# V-00797-00.net
KiCad netlist of a schematic drawn in EAGLE
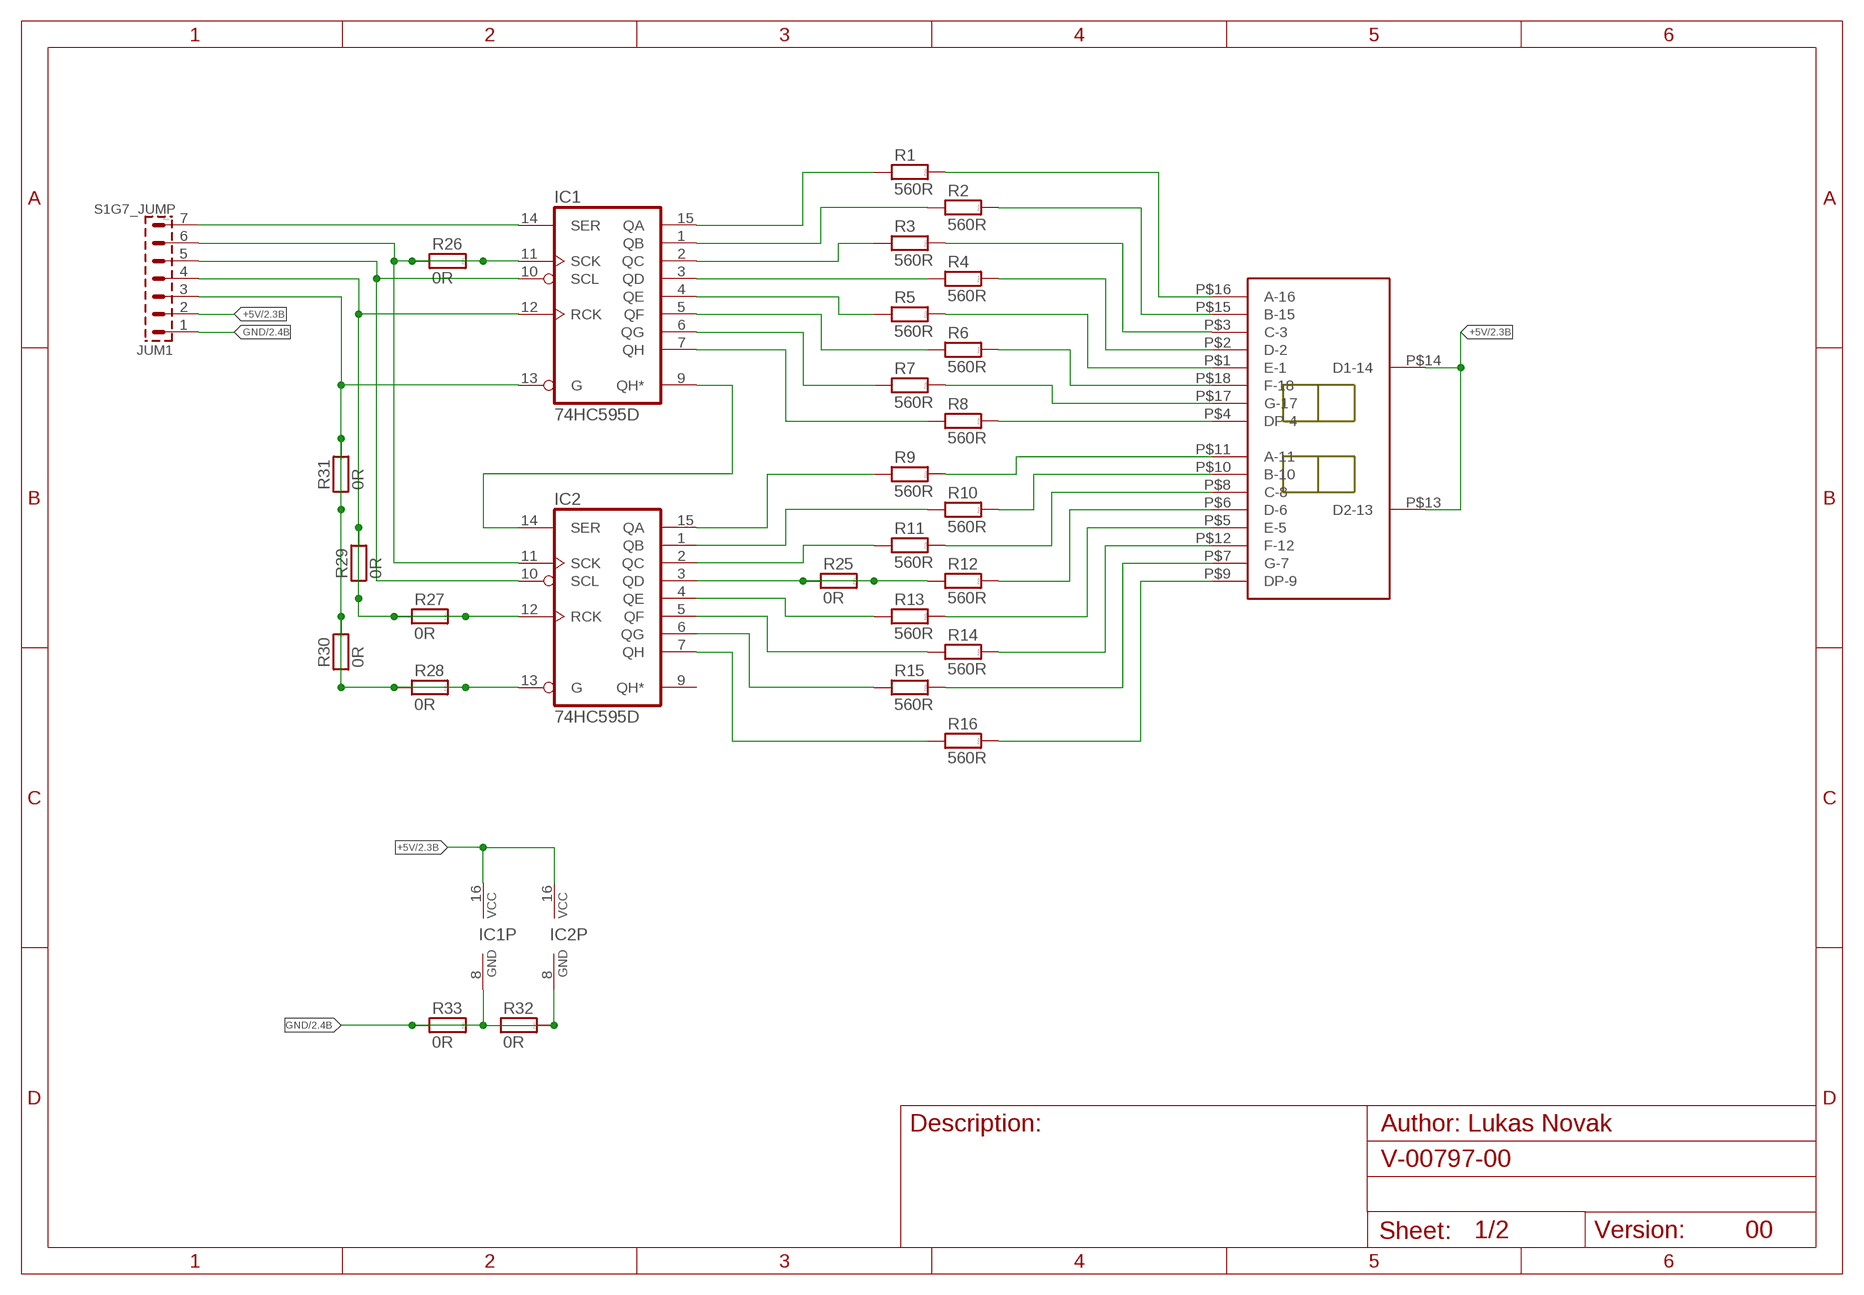
[diagram p0: schematic, sheet 1]
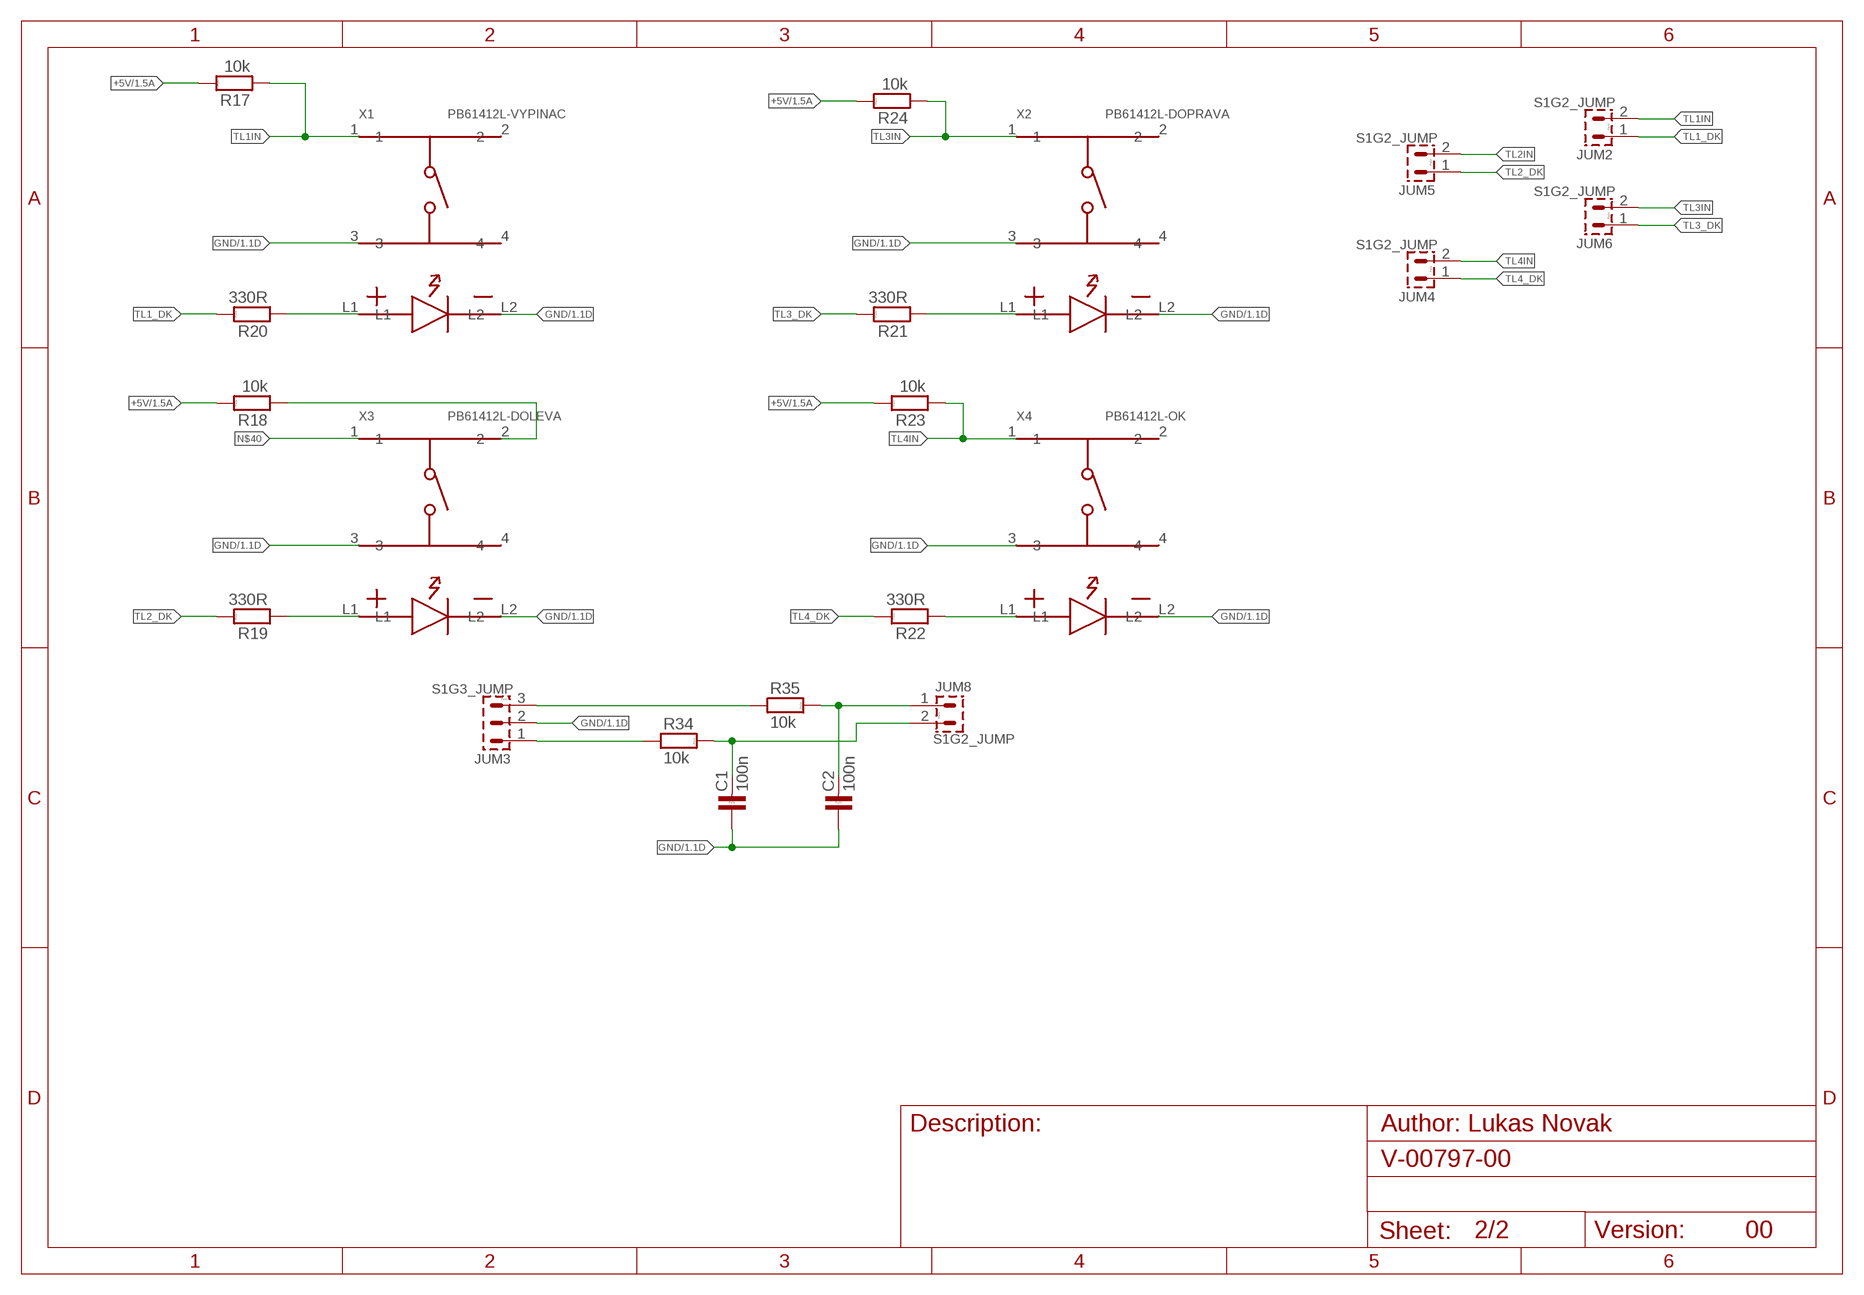
[diagram p1: schematic, sheet 2]

(export (version "E")
  (design (tool "Eeschema 10.0.6"))
  (components
    (comp (ref "IC1")
      (value "74HC595D")
      (footprint "eagle-import:SO16")
      (libsource (lib "eagle-import") (part "74595DHC"))
    )
    (comp (ref "IC2")
      (value "74HC595D")
      (footprint "eagle-import:SO16")
      (libsource (lib "eagle-import") (part "74595DHC"))
    )
    (comp (ref "JUM1")
      (value "S1G7_JUMP")
      (footprint "eagle-import:S1G7_JUM")
      (libsource (lib "eagle-import") (part "S1G7_JUMP"))
    )
    (comp (ref "R1")
      (value "560R")
      (footprint "eagle-import:1206")
      (libsource (lib "eagle-import") (part "R_1206"))
    )
    (comp (ref "R2")
      (value "560R")
      (footprint "eagle-import:1206")
      (libsource (lib "eagle-import") (part "R_1206"))
    )
    (comp (ref "R3")
      (value "560R")
      (footprint "eagle-import:1206")
      (libsource (lib "eagle-import") (part "R_1206"))
    )
    (comp (ref "R4")
      (value "560R")
      (footprint "eagle-import:1206")
      (libsource (lib "eagle-import") (part "R_1206"))
    )
    (comp (ref "R5")
      (value "560R")
      (footprint "eagle-import:1206")
      (libsource (lib "eagle-import") (part "R_1206"))
    )
    (comp (ref "R6")
      (value "560R")
      (footprint "eagle-import:1206")
      (libsource (lib "eagle-import") (part "R_1206"))
    )
    (comp (ref "R7")
      (value "560R")
      (footprint "eagle-import:1206")
      (libsource (lib "eagle-import") (part "R_1206"))
    )
    (comp (ref "R8")
      (value "560R")
      (footprint "eagle-import:1206")
      (libsource (lib "eagle-import") (part "R_1206"))
    )
    (comp (ref "R9")
      (value "560R")
      (footprint "eagle-import:1206")
      (libsource (lib "eagle-import") (part "R_1206"))
    )
    (comp (ref "R10")
      (value "560R")
      (footprint "eagle-import:1206")
      (libsource (lib "eagle-import") (part "R_1206"))
    )
    (comp (ref "R11")
      (value "560R")
      (footprint "eagle-import:1206")
      (libsource (lib "eagle-import") (part "R_1206"))
    )
    (comp (ref "R12")
      (value "560R")
      (footprint "eagle-import:1206")
      (libsource (lib "eagle-import") (part "R_1206"))
    )
    (comp (ref "R13")
      (value "560R")
      (footprint "eagle-import:1206")
      (libsource (lib "eagle-import") (part "R_1206"))
    )
    (comp (ref "R14")
      (value "560R")
      (footprint "eagle-import:1206")
      (libsource (lib "eagle-import") (part "R_1206"))
    )
    (comp (ref "R15")
      (value "560R")
      (footprint "eagle-import:1206")
      (libsource (lib "eagle-import") (part "R_1206"))
    )
    (comp (ref "R16")
      (value "560R")
      (footprint "eagle-import:1206")
      (libsource (lib "eagle-import") (part "R_1206"))
    )
    (comp (ref "R25")
      (value "0R")
      (footprint "eagle-import:1206")
      (libsource (lib "eagle-import") (part "R_1206"))
    )
    (comp (ref "R26")
      (value "0R")
      (footprint "eagle-import:1206")
      (libsource (lib "eagle-import") (part "R_1206"))
    )
    (comp (ref "R27")
      (value "0R")
      (footprint "eagle-import:1206")
      (libsource (lib "eagle-import") (part "R_1206"))
    )
    (comp (ref "R28")
      (value "0R")
      (footprint "eagle-import:1206")
      (libsource (lib "eagle-import") (part "R_1206"))
    )
    (comp (ref "R29")
      (value "0R")
      (footprint "eagle-import:1206")
      (libsource (lib "eagle-import") (part "R_1206"))
    )
    (comp (ref "R30")
      (value "0R")
      (footprint "eagle-import:1206")
      (libsource (lib "eagle-import") (part "R_1206"))
    )
    (comp (ref "R31")
      (value "0R")
      (footprint "eagle-import:1206")
      (libsource (lib "eagle-import") (part "R_1206"))
    )
    (comp (ref "R32")
      (value "0R")
      (footprint "eagle-import:1206")
      (libsource (lib "eagle-import") (part "R_1206"))
    )
    (comp (ref "R33")
      (value "0R")
      (footprint "eagle-import:1206")
      (libsource (lib "eagle-import") (part "R_1206"))
    )
    (comp (ref "U$1")
      (value "BD-A544RD")
      (footprint "eagle-import:BD-A544RD")
      (libsource (lib "eagle-import") (part "BD-A544RD"))
    )
    (comp (ref "C1")
      (value "100n")
      (footprint "eagle-import:1206")
      (libsource (lib "eagle-import") (part "C-KER_1206"))
    )
    (comp (ref "C2")
      (value "100n")
      (footprint "eagle-import:1206")
      (libsource (lib "eagle-import") (part "C-KER_1206"))
    )
    (comp (ref "JUM2")
      (value "S1G2_JUMP")
      (footprint "eagle-import:S1G2_JUM")
      (libsource (lib "eagle-import") (part "S1G2_JUMP"))
    )
    (comp (ref "JUM3")
      (value "S1G3_JUMP")
      (footprint "eagle-import:S1G3_JUM")
      (libsource (lib "eagle-import") (part "S1G3_JUMP"))
    )
    (comp (ref "JUM4")
      (value "S1G2_JUMP")
      (footprint "eagle-import:S1G2_JUM")
      (libsource (lib "eagle-import") (part "S1G2_JUMP"))
    )
    (comp (ref "JUM5")
      (value "S1G2_JUMP")
      (footprint "eagle-import:S1G2_JUM")
      (libsource (lib "eagle-import") (part "S1G2_JUMP"))
    )
    (comp (ref "JUM6")
      (value "S1G2_JUMP")
      (footprint "eagle-import:S1G2_JUM")
      (libsource (lib "eagle-import") (part "S1G2_JUMP"))
    )
    (comp (ref "JUM8")
      (value "S1G2_JUMP")
      (footprint "eagle-import:S1G2_JUM")
      (libsource (lib "eagle-import") (part "S1G2_JUMP"))
    )
    (comp (ref "R17")
      (value "10k")
      (footprint "eagle-import:1206")
      (libsource (lib "eagle-import") (part "R_1206"))
    )
    (comp (ref "R18")
      (value "10k")
      (footprint "eagle-import:1206")
      (libsource (lib "eagle-import") (part "R_1206"))
    )
    (comp (ref "R19")
      (value "330R")
      (footprint "eagle-import:1206")
      (libsource (lib "eagle-import") (part "R_1206"))
    )
    (comp (ref "R20")
      (value "330R")
      (footprint "eagle-import:1206")
      (libsource (lib "eagle-import") (part "R_1206"))
    )
    (comp (ref "R21")
      (value "330R")
      (footprint "eagle-import:1206")
      (libsource (lib "eagle-import") (part "R_1206"))
    )
    (comp (ref "R22")
      (value "330R")
      (footprint "eagle-import:1206")
      (libsource (lib "eagle-import") (part "R_1206"))
    )
    (comp (ref "R23")
      (value "10k")
      (footprint "eagle-import:1206")
      (libsource (lib "eagle-import") (part "R_1206"))
    )
    (comp (ref "R24")
      (value "10k")
      (footprint "eagle-import:1206")
      (libsource (lib "eagle-import") (part "R_1206"))
    )
    (comp (ref "R34")
      (value "10k")
      (footprint "eagle-import:1206")
      (libsource (lib "eagle-import") (part "R_1206"))
    )
    (comp (ref "R35")
      (value "10k")
      (footprint "eagle-import:1206")
      (libsource (lib "eagle-import") (part "R_1206"))
    )
    (comp (ref "X1")
      (value "PB61412L-VYPINAC")
      (footprint "eagle-import:PB1412L-101")
      (libsource (lib "eagle-import") (part "PB61412L-NEUTRAL"))
    )
    (comp (ref "X2")
      (value "PB61412L-DOPRAVA")
      (footprint "eagle-import:PB1412L-101")
      (libsource (lib "eagle-import") (part "PB61412L-NEUTRAL"))
    )
    (comp (ref "X3")
      (value "PB61412L-DOLEVA")
      (footprint "eagle-import:PB1412L-101")
      (libsource (lib "eagle-import") (part "PB61412L-NEUTRAL"))
    )
    (comp (ref "X4")
      (value "PB61412L-OK")
      (footprint "eagle-import:PB1412L-101")
      (libsource (lib "eagle-import") (part "PB61412L-NEUTRAL"))
    )
  )
  (nets
    (net (code "1") (name "+5V") (class "Default")
      (node (ref "IC1") (pin "16") (pinfunction "VCC_16") (pintype "power_in"))
      (node (ref "IC2") (pin "16") (pinfunction "VCC_16") (pintype "power_in"))
      (node (ref "JUM1") (pin "2") (pinfunction "2_2") (pintype "passive"))
      (node (ref "R17") (pin "2") (pinfunction "2_2") (pintype "passive"))
      (node (ref "R18") (pin "2") (pinfunction "2_2") (pintype "passive"))
      (node (ref "R23") (pin "2") (pinfunction "2_2") (pintype "passive"))
      (node (ref "R24") (pin "2") (pinfunction "2_2") (pintype "passive"))
      (node (ref "U$1") (pin "P$13") (pinfunction "D2-13_P$13") (pintype "bidirectional"))
      (node (ref "U$1") (pin "P$14") (pinfunction "D1-14_P$14") (pintype "bidirectional"))
    )
    (net (code "2") (name "GND") (class "Default")
      (node (ref "C1") (pin "1") (pinfunction "1_1") (pintype "passive"))
      (node (ref "C2") (pin "1") (pinfunction "1_1") (pintype "passive"))
      (node (ref "IC1") (pin "8") (pinfunction "GND_8") (pintype "power_in"))
      (node (ref "IC2") (pin "8") (pinfunction "GND_8") (pintype "power_in"))
      (node (ref "JUM1") (pin "1") (pinfunction "1_1") (pintype "passive"))
      (node (ref "JUM3") (pin "2") (pinfunction "2_2") (pintype "passive"))
      (node (ref "R32") (pin "1") (pinfunction "1_1") (pintype "passive"))
      (node (ref "R32") (pin "2") (pinfunction "2_2") (pintype "passive"))
      (node (ref "R33") (pin "1") (pinfunction "1_1") (pintype "passive"))
      (node (ref "R33") (pin "2") (pinfunction "2_2") (pintype "passive"))
      (node (ref "X1") (pin "3") (pinfunction "3_3") (pintype "bidirectional"))
      (node (ref "X1") (pin "L2") (pinfunction "L2_L2") (pintype "bidirectional"))
      (node (ref "X2") (pin "3") (pinfunction "3_3") (pintype "bidirectional"))
      (node (ref "X2") (pin "L2") (pinfunction "L2_L2") (pintype "bidirectional"))
      (node (ref "X3") (pin "3") (pinfunction "3_3") (pintype "bidirectional"))
      (node (ref "X3") (pin "L2") (pinfunction "L2_L2") (pintype "bidirectional"))
      (node (ref "X4") (pin "3") (pinfunction "3_3") (pintype "bidirectional"))
      (node (ref "X4") (pin "L2") (pinfunction "L2_L2") (pintype "bidirectional"))
    )
    (net (code "3") (name "N$40") (class "Default")
      (node (ref "X3") (pin "1") (pinfunction "1_1") (pintype "bidirectional"))
    )
    (net (code "4") (name "Net-(C1-Pad2)") (class "Default")
      (node (ref "C1") (pin "2") (pinfunction "2_2") (pintype "passive"))
      (node (ref "JUM8") (pin "2") (pinfunction "2_2") (pintype "passive"))
      (node (ref "R34") (pin "2") (pinfunction "2_2") (pintype "passive"))
    )
    (net (code "5") (name "Net-(C2-Pad2)") (class "Default")
      (node (ref "C2") (pin "2") (pinfunction "2_2") (pintype "passive"))
      (node (ref "JUM8") (pin "1") (pinfunction "1_1") (pintype "passive"))
      (node (ref "R35") (pin "2") (pinfunction "2_2") (pintype "passive"))
    )
    (net (code "6") (name "Net-(IC1A-G)") (class "Default")
      (node (ref "IC1") (pin "13") (pinfunction "G_13") (pintype "input"))
      (node (ref "IC2") (pin "13") (pinfunction "G_13") (pintype "input"))
      (node (ref "JUM1") (pin "3") (pinfunction "3_3") (pintype "passive"))
      (node (ref "R28") (pin "1") (pinfunction "1_1") (pintype "passive"))
      (node (ref "R28") (pin "2") (pinfunction "2_2") (pintype "passive"))
      (node (ref "R30") (pin "1") (pinfunction "1_1") (pintype "passive"))
      (node (ref "R30") (pin "2") (pinfunction "2_2") (pintype "passive"))
      (node (ref "R31") (pin "1") (pinfunction "1_1") (pintype "passive"))
      (node (ref "R31") (pin "2") (pinfunction "2_2") (pintype "passive"))
    )
    (net (code "7") (name "Net-(IC1A-QA)") (class "Default")
      (node (ref "IC1") (pin "15") (pinfunction "QA_15") (pintype "tri_state"))
      (node (ref "R1") (pin "1") (pinfunction "1_1") (pintype "passive"))
    )
    (net (code "8") (name "Net-(IC1A-QB)") (class "Default")
      (node (ref "IC1") (pin "1") (pinfunction "QB_1") (pintype "tri_state"))
      (node (ref "R2") (pin "1") (pinfunction "1_1") (pintype "passive"))
    )
    (net (code "9") (name "Net-(IC1A-QC)") (class "Default")
      (node (ref "IC1") (pin "2") (pinfunction "QC_2") (pintype "tri_state"))
      (node (ref "R3") (pin "1") (pinfunction "1_1") (pintype "passive"))
    )
    (net (code "10") (name "Net-(IC1A-QD)") (class "Default")
      (node (ref "IC1") (pin "3") (pinfunction "QD_3") (pintype "tri_state"))
      (node (ref "R4") (pin "1") (pinfunction "1_1") (pintype "passive"))
    )
    (net (code "11") (name "Net-(IC1A-QE)") (class "Default")
      (node (ref "IC1") (pin "4") (pinfunction "QE_4") (pintype "tri_state"))
      (node (ref "R5") (pin "1") (pinfunction "1_1") (pintype "passive"))
    )
    (net (code "12") (name "Net-(IC1A-QF)") (class "Default")
      (node (ref "IC1") (pin "5") (pinfunction "QF_5") (pintype "tri_state"))
      (node (ref "R6") (pin "1") (pinfunction "1_1") (pintype "passive"))
    )
    (net (code "13") (name "Net-(IC1A-QG)") (class "Default")
      (node (ref "IC1") (pin "6") (pinfunction "QG_6") (pintype "tri_state"))
      (node (ref "R7") (pin "1") (pinfunction "1_1") (pintype "passive"))
    )
    (net (code "14") (name "Net-(IC1A-QH)") (class "Default")
      (node (ref "IC1") (pin "7") (pinfunction "QH_7") (pintype "tri_state"))
      (node (ref "R8") (pin "1") (pinfunction "1_1") (pintype "passive"))
    )
    (net (code "15") (name "Net-(IC1A-QH*)") (class "Default")
      (node (ref "IC1") (pin "9") (pinfunction "QH*_9") (pintype "tri_state"))
      (node (ref "IC2") (pin "14") (pinfunction "SER_14") (pintype "input"))
    )
    (net (code "16") (name "Net-(IC1A-RCK)") (class "Default")
      (node (ref "IC1") (pin "12") (pinfunction "RCK_12") (pintype "input"))
      (node (ref "IC2") (pin "12") (pinfunction "RCK_12") (pintype "input"))
      (node (ref "JUM1") (pin "4") (pinfunction "4_4") (pintype "passive"))
      (node (ref "R27") (pin "1") (pinfunction "1_1") (pintype "passive"))
      (node (ref "R27") (pin "2") (pinfunction "2_2") (pintype "passive"))
      (node (ref "R29") (pin "1") (pinfunction "1_1") (pintype "passive"))
      (node (ref "R29") (pin "2") (pinfunction "2_2") (pintype "passive"))
    )
    (net (code "17") (name "Net-(IC1A-SCK)") (class "Default")
      (node (ref "IC1") (pin "11") (pinfunction "SCK_11") (pintype "input"))
      (node (ref "IC2") (pin "11") (pinfunction "SCK_11") (pintype "input"))
      (node (ref "JUM1") (pin "6") (pinfunction "6_6") (pintype "passive"))
      (node (ref "R26") (pin "1") (pinfunction "1_1") (pintype "passive"))
      (node (ref "R26") (pin "2") (pinfunction "2_2") (pintype "passive"))
    )
    (net (code "18") (name "Net-(IC1A-SCL)") (class "Default")
      (node (ref "IC1") (pin "10") (pinfunction "SCL_10") (pintype "input"))
      (node (ref "IC2") (pin "10") (pinfunction "SCL_10") (pintype "input"))
      (node (ref "JUM1") (pin "5") (pinfunction "5_5") (pintype "passive"))
    )
    (net (code "19") (name "Net-(IC1A-SER)") (class "Default")
      (node (ref "IC1") (pin "14") (pinfunction "SER_14") (pintype "input"))
      (node (ref "JUM1") (pin "7") (pinfunction "7_7") (pintype "passive"))
    )
    (net (code "20") (name "Net-(IC2A-QA)") (class "Default")
      (node (ref "IC2") (pin "15") (pinfunction "QA_15") (pintype "tri_state"))
      (node (ref "R9") (pin "1") (pinfunction "1_1") (pintype "passive"))
    )
    (net (code "21") (name "Net-(IC2A-QB)") (class "Default")
      (node (ref "IC2") (pin "1") (pinfunction "QB_1") (pintype "tri_state"))
      (node (ref "R10") (pin "1") (pinfunction "1_1") (pintype "passive"))
    )
    (net (code "22") (name "Net-(IC2A-QC)") (class "Default")
      (node (ref "IC2") (pin "2") (pinfunction "QC_2") (pintype "tri_state"))
      (node (ref "R11") (pin "1") (pinfunction "1_1") (pintype "passive"))
    )
    (net (code "23") (name "Net-(IC2A-QD)") (class "Default")
      (node (ref "IC2") (pin "3") (pinfunction "QD_3") (pintype "tri_state"))
      (node (ref "R12") (pin "1") (pinfunction "1_1") (pintype "passive"))
      (node (ref "R25") (pin "1") (pinfunction "1_1") (pintype "passive"))
      (node (ref "R25") (pin "2") (pinfunction "2_2") (pintype "passive"))
    )
    (net (code "24") (name "Net-(IC2A-QE)") (class "Default")
      (node (ref "IC2") (pin "4") (pinfunction "QE_4") (pintype "tri_state"))
      (node (ref "R13") (pin "1") (pinfunction "1_1") (pintype "passive"))
    )
    (net (code "25") (name "Net-(IC2A-QF)") (class "Default")
      (node (ref "IC2") (pin "5") (pinfunction "QF_5") (pintype "tri_state"))
      (node (ref "R14") (pin "1") (pinfunction "1_1") (pintype "passive"))
    )
    (net (code "26") (name "Net-(IC2A-QG)") (class "Default")
      (node (ref "IC2") (pin "6") (pinfunction "QG_6") (pintype "tri_state"))
      (node (ref "R15") (pin "1") (pinfunction "1_1") (pintype "passive"))
    )
    (net (code "27") (name "Net-(IC2A-QH)") (class "Default")
      (node (ref "IC2") (pin "7") (pinfunction "QH_7") (pintype "tri_state"))
      (node (ref "R16") (pin "1") (pinfunction "1_1") (pintype "passive"))
    )
    (net (code "28") (name "Net-(JUM3-Pad1)") (class "Default")
      (node (ref "JUM3") (pin "1") (pinfunction "1_1") (pintype "passive"))
      (node (ref "R34") (pin "1") (pinfunction "1_1") (pintype "passive"))
    )
    (net (code "29") (name "Net-(JUM3-Pad3)") (class "Default")
      (node (ref "JUM3") (pin "3") (pinfunction "3_3") (pintype "passive"))
      (node (ref "R35") (pin "1") (pinfunction "1_1") (pintype "passive"))
    )
    (net (code "30") (name "Net-(R19-Pad1)") (class "Default")
      (node (ref "R19") (pin "1") (pinfunction "1_1") (pintype "passive"))
      (node (ref "X3") (pin "L1") (pinfunction "L1_L1") (pintype "bidirectional"))
    )
    (net (code "31") (name "Net-(R20-Pad1)") (class "Default")
      (node (ref "R20") (pin "1") (pinfunction "1_1") (pintype "passive"))
      (node (ref "X1") (pin "L1") (pinfunction "L1_L1") (pintype "bidirectional"))
    )
    (net (code "32") (name "Net-(R21-Pad1)") (class "Default")
      (node (ref "R21") (pin "1") (pinfunction "1_1") (pintype "passive"))
      (node (ref "X2") (pin "L1") (pinfunction "L1_L1") (pintype "bidirectional"))
    )
    (net (code "33") (name "Net-(R22-Pad1)") (class "Default")
      (node (ref "R22") (pin "1") (pinfunction "1_1") (pintype "passive"))
      (node (ref "X4") (pin "L1") (pinfunction "L1_L1") (pintype "bidirectional"))
    )
    (net (code "34") (name "Net-(U$1-A-11)") (class "Default")
      (node (ref "R9") (pin "2") (pinfunction "2_2") (pintype "passive"))
      (node (ref "U$1") (pin "P$11") (pinfunction "A-11_P$11") (pintype "bidirectional"))
    )
    (net (code "35") (name "Net-(U$1-A-16)") (class "Default")
      (node (ref "R1") (pin "2") (pinfunction "2_2") (pintype "passive"))
      (node (ref "U$1") (pin "P$16") (pinfunction "A-16_P$16") (pintype "bidirectional"))
    )
    (net (code "36") (name "Net-(U$1-B-10)") (class "Default")
      (node (ref "R10") (pin "2") (pinfunction "2_2") (pintype "passive"))
      (node (ref "U$1") (pin "P$10") (pinfunction "B-10_P$10") (pintype "bidirectional"))
    )
    (net (code "37") (name "Net-(U$1-B-15)") (class "Default")
      (node (ref "R2") (pin "2") (pinfunction "2_2") (pintype "passive"))
      (node (ref "U$1") (pin "P$15") (pinfunction "B-15_P$15") (pintype "bidirectional"))
    )
    (net (code "38") (name "Net-(U$1-C-3)") (class "Default")
      (node (ref "R3") (pin "2") (pinfunction "2_2") (pintype "passive"))
      (node (ref "U$1") (pin "P$3") (pinfunction "C-3_P$3") (pintype "bidirectional"))
    )
    (net (code "39") (name "Net-(U$1-C-8)") (class "Default")
      (node (ref "R11") (pin "2") (pinfunction "2_2") (pintype "passive"))
      (node (ref "U$1") (pin "P$8") (pinfunction "C-8_P$8") (pintype "bidirectional"))
    )
    (net (code "40") (name "Net-(U$1-D-2)") (class "Default")
      (node (ref "R4") (pin "2") (pinfunction "2_2") (pintype "passive"))
      (node (ref "U$1") (pin "P$2") (pinfunction "D-2_P$2") (pintype "bidirectional"))
    )
    (net (code "41") (name "Net-(U$1-D-6)") (class "Default")
      (node (ref "R12") (pin "2") (pinfunction "2_2") (pintype "passive"))
      (node (ref "U$1") (pin "P$6") (pinfunction "D-6_P$6") (pintype "bidirectional"))
    )
    (net (code "42") (name "Net-(U$1-DP-4)") (class "Default")
      (node (ref "R8") (pin "2") (pinfunction "2_2") (pintype "passive"))
      (node (ref "U$1") (pin "P$4") (pinfunction "DP-4_P$4") (pintype "bidirectional"))
    )
    (net (code "43") (name "Net-(U$1-DP-9)") (class "Default")
      (node (ref "R16") (pin "2") (pinfunction "2_2") (pintype "passive"))
      (node (ref "U$1") (pin "P$9") (pinfunction "DP-9_P$9") (pintype "bidirectional"))
    )
    (net (code "44") (name "Net-(U$1-E-1)") (class "Default")
      (node (ref "R5") (pin "2") (pinfunction "2_2") (pintype "passive"))
      (node (ref "U$1") (pin "P$1") (pinfunction "E-1_P$1") (pintype "bidirectional"))
    )
    (net (code "45") (name "Net-(U$1-E-5)") (class "Default")
      (node (ref "R13") (pin "2") (pinfunction "2_2") (pintype "passive"))
      (node (ref "U$1") (pin "P$5") (pinfunction "E-5_P$5") (pintype "bidirectional"))
    )
    (net (code "46") (name "Net-(U$1-F-12)") (class "Default")
      (node (ref "R14") (pin "2") (pinfunction "2_2") (pintype "passive"))
      (node (ref "U$1") (pin "P$12") (pinfunction "F-12_P$12") (pintype "bidirectional"))
    )
    (net (code "47") (name "Net-(U$1-F-18)") (class "Default")
      (node (ref "R6") (pin "2") (pinfunction "2_2") (pintype "passive"))
      (node (ref "U$1") (pin "P$18") (pinfunction "F-18_P$18") (pintype "bidirectional"))
    )
    (net (code "48") (name "Net-(U$1-G-7)") (class "Default")
      (node (ref "R15") (pin "2") (pinfunction "2_2") (pintype "passive"))
      (node (ref "U$1") (pin "P$7") (pinfunction "G-7_P$7") (pintype "bidirectional"))
    )
    (net (code "49") (name "Net-(U$1-G-17)") (class "Default")
      (node (ref "R7") (pin "2") (pinfunction "2_2") (pintype "passive"))
      (node (ref "U$1") (pin "P$17") (pinfunction "G-17_P$17") (pintype "bidirectional"))
    )
    (net (code "50") (name "TL1IN") (class "Default")
      (node (ref "JUM2") (pin "2") (pinfunction "2_2") (pintype "passive"))
      (node (ref "R17") (pin "1") (pinfunction "1_1") (pintype "passive"))
      (node (ref "X1") (pin "1") (pinfunction "1_1") (pintype "bidirectional"))
    )
    (net (code "51") (name "TL1_DK") (class "Default")
      (node (ref "JUM2") (pin "1") (pinfunction "1_1") (pintype "passive"))
      (node (ref "R20") (pin "2") (pinfunction "2_2") (pintype "passive"))
    )
    (net (code "52") (name "TL2IN") (class "Default")
      (node (ref "JUM5") (pin "2") (pinfunction "2_2") (pintype "passive"))
      (node (ref "R18") (pin "1") (pinfunction "1_1") (pintype "passive"))
      (node (ref "X3") (pin "2") (pinfunction "2_2") (pintype "bidirectional"))
    )
    (net (code "53") (name "TL2_DK") (class "Default")
      (node (ref "JUM5") (pin "1") (pinfunction "1_1") (pintype "passive"))
      (node (ref "R19") (pin "2") (pinfunction "2_2") (pintype "passive"))
    )
    (net (code "54") (name "TL3IN") (class "Default")
      (node (ref "JUM6") (pin "2") (pinfunction "2_2") (pintype "passive"))
      (node (ref "R24") (pin "1") (pinfunction "1_1") (pintype "passive"))
      (node (ref "X2") (pin "1") (pinfunction "1_1") (pintype "bidirectional"))
    )
    (net (code "55") (name "TL3_DK") (class "Default")
      (node (ref "JUM6") (pin "1") (pinfunction "1_1") (pintype "passive"))
      (node (ref "R21") (pin "2") (pinfunction "2_2") (pintype "passive"))
    )
    (net (code "56") (name "TL4IN") (class "Default")
      (node (ref "JUM4") (pin "2") (pinfunction "2_2") (pintype "passive"))
      (node (ref "R23") (pin "1") (pinfunction "1_1") (pintype "passive"))
      (node (ref "X4") (pin "1") (pinfunction "1_1") (pintype "bidirectional"))
    )
    (net (code "57") (name "TL4_DK") (class "Default")
      (node (ref "JUM4") (pin "1") (pinfunction "1_1") (pintype "passive"))
      (node (ref "R22") (pin "2") (pinfunction "2_2") (pintype "passive"))
    )
    (net (code "58") (name "unconnected-(IC2A-QH*-Pad9)") (class "Default")
      (node (ref "IC2") (pin "9") (pinfunction "QH*_9") (pintype "tri_state"))
    )
    (net (code "59") (name "unconnected-(X1-Pad2)") (class "Default")
      (node (ref "X1") (pin "2") (pinfunction "2_2") (pintype "bidirectional"))
    )
    (net (code "60") (name "unconnected-(X1-Pad4)") (class "Default")
      (node (ref "X1") (pin "4") (pinfunction "4_4") (pintype "bidirectional"))
    )
    (net (code "61") (name "unconnected-(X2-Pad2)") (class "Default")
      (node (ref "X2") (pin "2") (pinfunction "2_2") (pintype "bidirectional"))
    )
    (net (code "62") (name "unconnected-(X2-Pad4)") (class "Default")
      (node (ref "X2") (pin "4") (pinfunction "4_4") (pintype "bidirectional"))
    )
    (net (code "63") (name "unconnected-(X3-Pad4)") (class "Default")
      (node (ref "X3") (pin "4") (pinfunction "4_4") (pintype "bidirectional"))
    )
    (net (code "64") (name "unconnected-(X4-Pad2)") (class "Default")
      (node (ref "X4") (pin "2") (pinfunction "2_2") (pintype "bidirectional"))
    )
    (net (code "65") (name "unconnected-(X4-Pad4)") (class "Default")
      (node (ref "X4") (pin "4") (pinfunction "4_4") (pintype "bidirectional"))
    )
  )
)
